# 11_-_CPU_-_POWER.net
KiCad netlist of a schematic drawn in Altium Designer
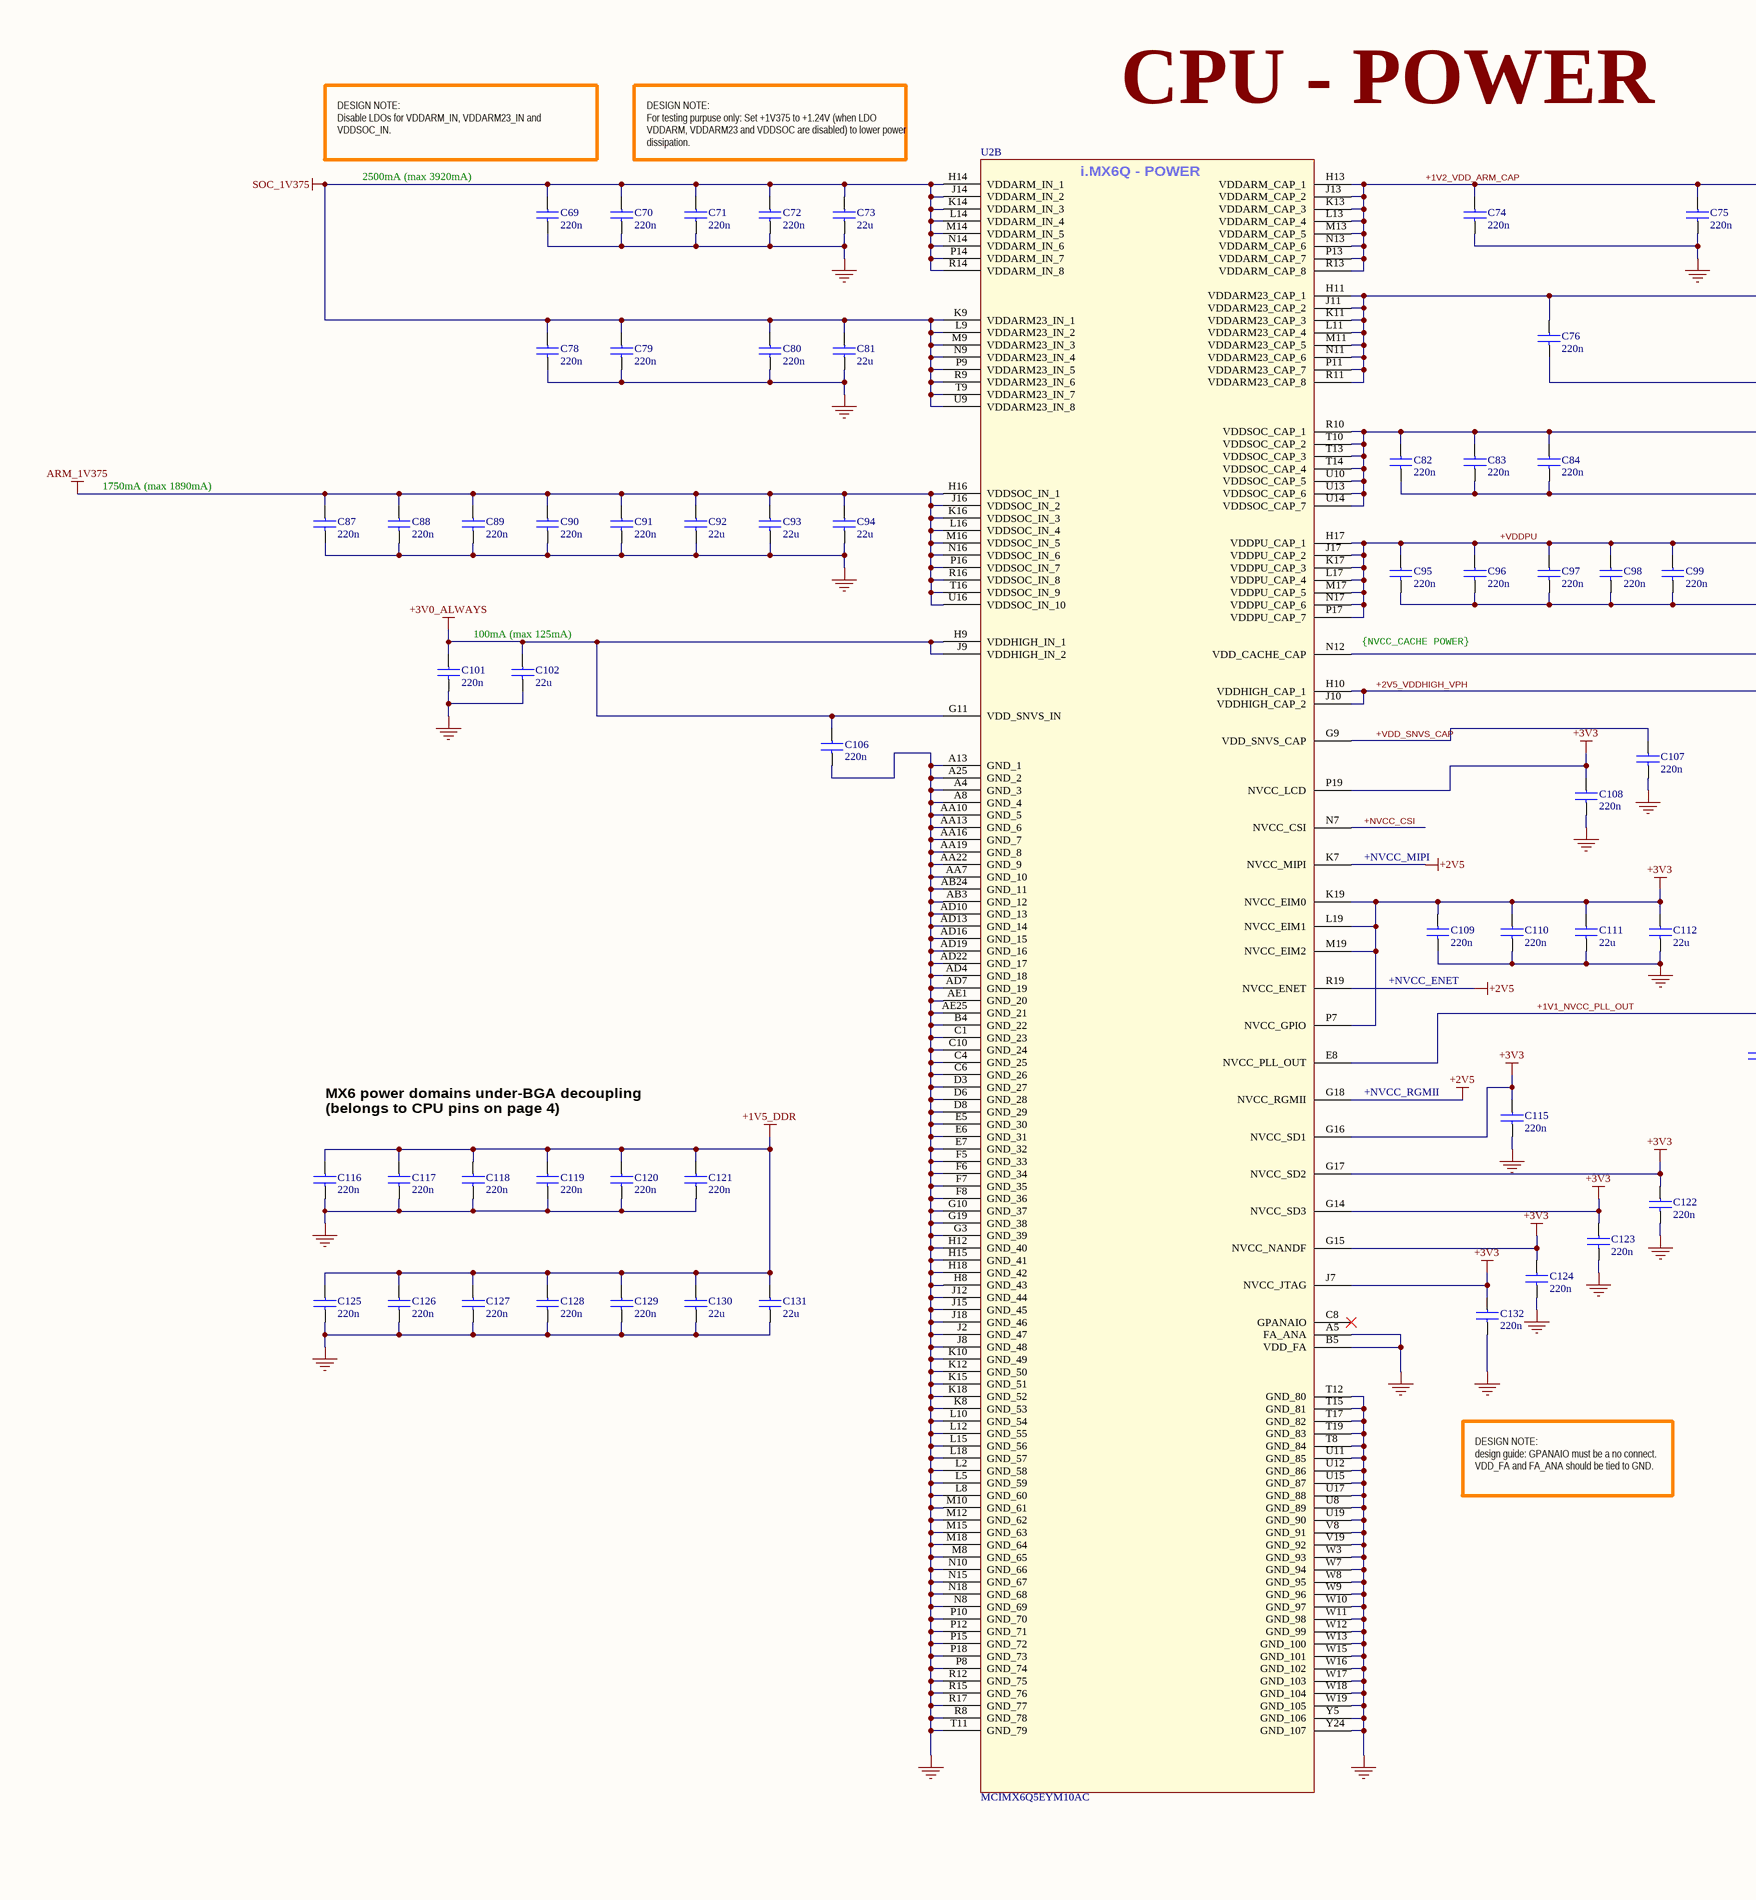
[diagram p0: [11] - CPU - POWER.SchDoc, left]
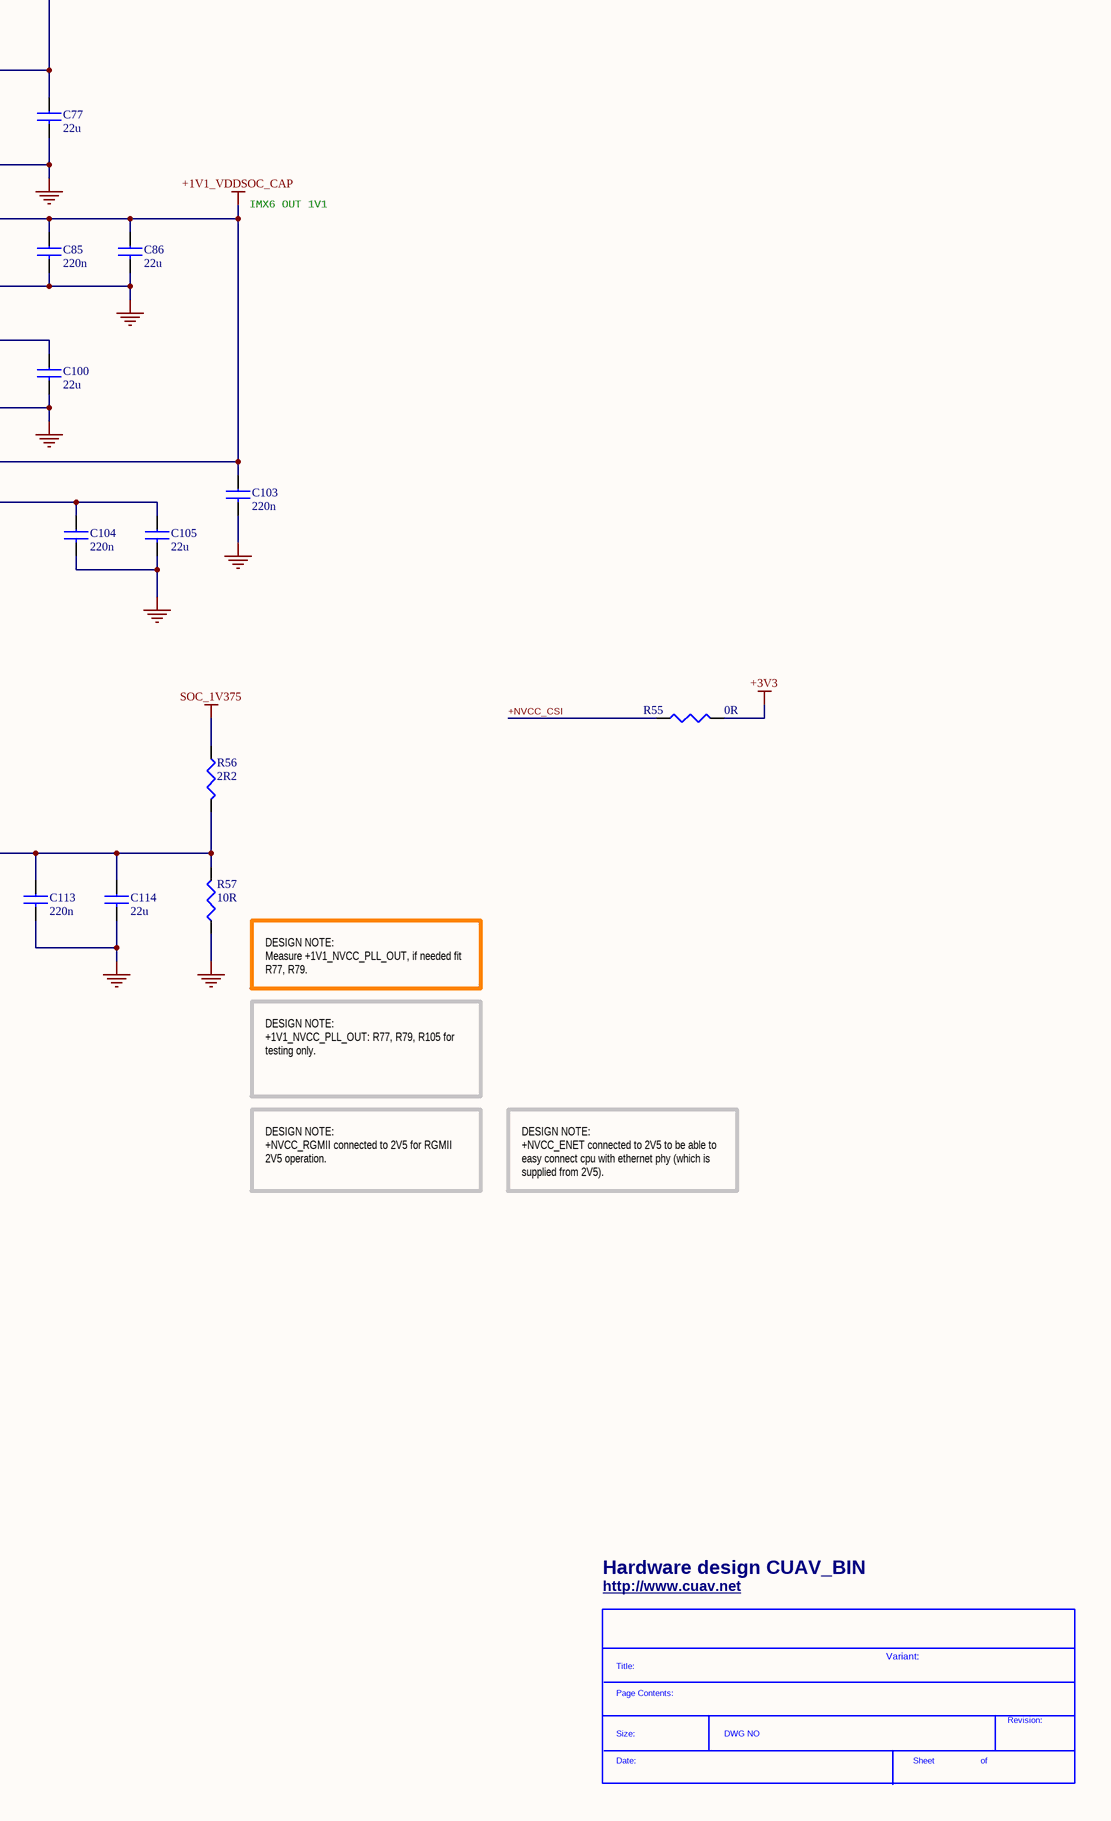
[diagram p1: [11] - CPU - POWER.SchDoc, right]

(export (version "E")
  (design (tool "Eeschema 10.0.6"))
  (components
    (comp (ref "*") (value "SDTitleBlock") (libsource (lib "*") (part "SDTitleBlock")))
    (comp (ref "C69")
      (value "220n")
      (footprint "0402cap")
      (description "CAP CER .22UF 25V X5R 20% 0402")
      (fields
        (field (name "MANUFACTURER") "TDK Corporation")
        (field (name "MANUFACTURER PART NUMBER") "C1005X5R1E224M")
      )
      (libsource (lib "Integrated_Library_RF_FEB_2012") (part "C1005X5R1E224M"))
    )
    (comp (ref "C70")
      (value "220n")
      (footprint "0402cap")
      (description "CAP CER .22UF 25V X5R 20% 0402")
      (fields
        (field (name "MANUFACTURER") "TDK Corporation")
        (field (name "MANUFACTURER PART NUMBER") "C1005X5R1E224M")
      )
      (libsource (lib "Integrated_Library_RF_FEB_2012") (part "C1005X5R1E224M"))
    )
    (comp (ref "C71")
      (value "220n")
      (footprint "0402cap")
      (description "CAP CER .22UF 25V X5R 20% 0402")
      (fields
        (field (name "MANUFACTURER") "TDK Corporation")
        (field (name "MANUFACTURER PART NUMBER") "C1005X5R1E224M")
      )
      (libsource (lib "Integrated_Library_RF_FEB_2012") (part "C1005X5R1E224M"))
    )
    (comp (ref "C72")
      (value "220n")
      (footprint "0402cap")
      (description "CAP CER .22UF 25V X5R 20% 0402")
      (fields
        (field (name "MANUFACTURER") "TDK Corporation")
        (field (name "MANUFACTURER PART NUMBER") "C1005X5R1E224M")
      )
      (libsource (lib "Integrated_Library_RF_FEB_2012") (part "C1005X5R1E224M"))
    )
    (comp (ref "C73")
      (value "22u")
      (footprint "C0603")
      (description "CAP CER 22UF 4V 20% X5R 0603")
      (fields
        (field (name "MANUFACTURER") "Murata Electronics North America")
        (field (name "MANUFACTURER PART NUMBER") "GRM188R60G226MEA0L")
        (field (name ".CHECKED PCB") "RF, used by MM")
        (field (name ".CHECKED SCH") "MM, checked by RF")
        (field (name ".CREATOR") "MM")
      )
      (libsource (lib "Schlib_RF") (part "GRM188R60G226MEA0L"))
    )
    (comp (ref "C74")
      (value "220n")
      (footprint "0402cap")
      (description "CAP CER .22UF 25V X5R 20% 0402")
      (fields
        (field (name "MANUFACTURER") "TDK Corporation")
        (field (name "MANUFACTURER PART NUMBER") "C1005X5R1E224M")
      )
      (libsource (lib "Integrated_Library_RF_FEB_2012") (part "C1005X5R1E224M"))
    )
    (comp (ref "C75")
      (value "220n")
      (footprint "0402cap")
      (description "CAP CER .22UF 25V X5R 20% 0402")
      (fields
        (field (name "MANUFACTURER") "TDK Corporation")
        (field (name "MANUFACTURER PART NUMBER") "C1005X5R1E224M")
      )
      (libsource (lib "Integrated_Library_RF_FEB_2012") (part "C1005X5R1E224M"))
    )
    (comp (ref "C76")
      (value "220n")
      (footprint "0402cap")
      (description "CAP CER .22UF 25V X5R 20% 0402")
      (fields
        (field (name "MANUFACTURER") "TDK Corporation")
        (field (name "MANUFACTURER PART NUMBER") "C1005X5R1E224M")
      )
      (libsource (lib "Integrated_Library_RF_FEB_2012") (part "C1005X5R1E224M"))
    )
    (comp (ref "C77")
      (value "22u")
      (footprint "C0603")
      (description "CAP CER 22UF 4V 20% X5R 0603")
      (fields
        (field (name "MANUFACTURER") "Murata Electronics North America")
        (field (name "MANUFACTURER PART NUMBER") "GRM188R60G226MEA0L")
        (field (name ".CHECKED PCB") "RF, used by MM")
        (field (name ".CHECKED SCH") "MM, checked by RF")
        (field (name ".CREATOR") "MM")
      )
      (libsource (lib "Schlib_RF") (part "GRM188R60G226MEA0L"))
    )
    (comp (ref "C78")
      (value "220n")
      (footprint "0402cap")
      (description "CAP CER .22UF 25V X5R 20% 0402")
      (fields
        (field (name "MANUFACTURER") "TDK Corporation")
        (field (name "MANUFACTURER PART NUMBER") "C1005X5R1E224M")
      )
      (libsource (lib "Integrated_Library_RF_FEB_2012") (part "C1005X5R1E224M"))
    )
    (comp (ref "C79")
      (value "220n")
      (footprint "0402cap")
      (description "CAP CER .22UF 25V X5R 20% 0402")
      (fields
        (field (name "MANUFACTURER") "TDK Corporation")
        (field (name "MANUFACTURER PART NUMBER") "C1005X5R1E224M")
      )
      (libsource (lib "Integrated_Library_RF_FEB_2012") (part "C1005X5R1E224M"))
    )
    (comp (ref "C80")
      (value "220n")
      (footprint "0402cap")
      (description "CAP CER .22UF 25V X5R 20% 0402")
      (fields
        (field (name "MANUFACTURER") "TDK Corporation")
        (field (name "MANUFACTURER PART NUMBER") "C1005X5R1E224M")
      )
      (libsource (lib "Integrated_Library_RF_FEB_2012") (part "C1005X5R1E224M"))
    )
    (comp (ref "C81")
      (value "22u")
      (footprint "C0603")
      (description "CAP CER 22UF 4V 20% X5R 0603")
      (fields
        (field (name "MANUFACTURER") "Murata Electronics North America")
        (field (name "MANUFACTURER PART NUMBER") "GRM188R60G226MEA0L")
        (field (name ".CHECKED PCB") "RF, used by MM")
        (field (name ".CHECKED SCH") "MM, checked by RF")
        (field (name ".CREATOR") "MM")
      )
      (libsource (lib "Schlib_RF") (part "GRM188R60G226MEA0L"))
    )
    (comp (ref "C82")
      (value "220n")
      (footprint "0402cap")
      (description "CAP CER .22UF 25V X5R 20% 0402")
      (fields
        (field (name "MANUFACTURER") "TDK Corporation")
        (field (name "MANUFACTURER PART NUMBER") "C1005X5R1E224M")
      )
      (libsource (lib "Integrated_Library_RF_FEB_2012") (part "C1005X5R1E224M"))
    )
    (comp (ref "C83")
      (value "220n")
      (footprint "0402cap")
      (description "CAP CER .22UF 25V X5R 20% 0402")
      (fields
        (field (name "MANUFACTURER") "TDK Corporation")
        (field (name "MANUFACTURER PART NUMBER") "C1005X5R1E224M")
      )
      (libsource (lib "Integrated_Library_RF_FEB_2012") (part "C1005X5R1E224M"))
    )
    (comp (ref "C84")
      (value "220n")
      (footprint "0402cap")
      (description "CAP CER .22UF 25V X5R 20% 0402")
      (fields
        (field (name "MANUFACTURER") "TDK Corporation")
        (field (name "MANUFACTURER PART NUMBER") "C1005X5R1E224M")
      )
      (libsource (lib "Integrated_Library_RF_FEB_2012") (part "C1005X5R1E224M"))
    )
    (comp (ref "C85")
      (value "220n")
      (footprint "0402cap")
      (description "CAP CER .22UF 25V X5R 20% 0402")
      (fields
        (field (name "MANUFACTURER") "TDK Corporation")
        (field (name "MANUFACTURER PART NUMBER") "C1005X5R1E224M")
      )
      (libsource (lib "Integrated_Library_RF_FEB_2012") (part "C1005X5R1E224M"))
    )
    (comp (ref "C86")
      (value "22u")
      (footprint "C0603")
      (description "CAP CER 22UF 4V 20% X5R 0603")
      (fields
        (field (name "MANUFACTURER") "Murata Electronics North America")
        (field (name "MANUFACTURER PART NUMBER") "GRM188R60G226MEA0L")
        (field (name ".CHECKED PCB") "RF, used by MM")
        (field (name ".CHECKED SCH") "MM, checked by RF")
        (field (name ".CREATOR") "MM")
      )
      (libsource (lib "Schlib_RF") (part "GRM188R60G226MEA0L"))
    )
    (comp (ref "C87")
      (value "220n")
      (footprint "0402cap")
      (description "CAP CER .22UF 25V X5R 20% 0402")
      (fields
        (field (name "MANUFACTURER") "TDK Corporation")
        (field (name "MANUFACTURER PART NUMBER") "C1005X5R1E224M")
      )
      (libsource (lib "Integrated_Library_RF_FEB_2012") (part "C1005X5R1E224M"))
    )
    (comp (ref "C88")
      (value "220n")
      (footprint "0402cap")
      (description "CAP CER .22UF 25V X5R 20% 0402")
      (fields
        (field (name "MANUFACTURER") "TDK Corporation")
        (field (name "MANUFACTURER PART NUMBER") "C1005X5R1E224M")
      )
      (libsource (lib "Integrated_Library_RF_FEB_2012") (part "C1005X5R1E224M"))
    )
    (comp (ref "C89")
      (value "220n")
      (footprint "0402cap")
      (description "CAP CER .22UF 25V X5R 20% 0402")
      (fields
        (field (name "MANUFACTURER") "TDK Corporation")
        (field (name "MANUFACTURER PART NUMBER") "C1005X5R1E224M")
      )
      (libsource (lib "Integrated_Library_RF_FEB_2012") (part "C1005X5R1E224M"))
    )
    (comp (ref "C90")
      (value "220n")
      (footprint "0402cap")
      (description "CAP CER .22UF 25V X5R 20% 0402")
      (fields
        (field (name "MANUFACTURER") "TDK Corporation")
        (field (name "MANUFACTURER PART NUMBER") "C1005X5R1E224M")
      )
      (libsource (lib "Integrated_Library_RF_FEB_2012") (part "C1005X5R1E224M"))
    )
    (comp (ref "C91")
      (value "220n")
      (footprint "0402cap")
      (description "CAP CER .22UF 25V X5R 20% 0402")
      (fields
        (field (name "MANUFACTURER") "TDK Corporation")
        (field (name "MANUFACTURER PART NUMBER") "C1005X5R1E224M")
      )
      (libsource (lib "Integrated_Library_RF_FEB_2012") (part "C1005X5R1E224M"))
    )
    (comp (ref "C92")
      (value "22u")
      (footprint "C0603")
      (description "CAP CER 22UF 4V 20% X5R 0603")
      (fields
        (field (name "MANUFACTURER") "Murata Electronics North America")
        (field (name "MANUFACTURER PART NUMBER") "GRM188R60G226MEA0L")
        (field (name ".CHECKED PCB") "RF, used by MM")
        (field (name ".CHECKED SCH") "MM, checked by RF")
        (field (name ".CREATOR") "MM")
      )
      (libsource (lib "Schlib_RF") (part "GRM188R60G226MEA0L"))
    )
    (comp (ref "C93")
      (value "22u")
      (footprint "C0603")
      (description "CAP CER 22UF 4V 20% X5R 0603")
      (fields
        (field (name "MANUFACTURER") "Murata Electronics North America")
        (field (name "MANUFACTURER PART NUMBER") "GRM188R60G226MEA0L")
        (field (name ".CHECKED PCB") "RF, used by MM")
        (field (name ".CHECKED SCH") "MM, checked by RF")
        (field (name ".CREATOR") "MM")
      )
      (libsource (lib "Schlib_RF") (part "GRM188R60G226MEA0L"))
    )
    (comp (ref "C94")
      (value "22u")
      (footprint "C0603")
      (description "CAP CER 22UF 4V 20% X5R 0603")
      (fields
        (field (name "MANUFACTURER") "Murata Electronics North America")
        (field (name "MANUFACTURER PART NUMBER") "GRM188R60G226MEA0L")
        (field (name ".CHECKED PCB") "RF, used by MM")
        (field (name ".CHECKED SCH") "MM, checked by RF")
        (field (name ".CREATOR") "MM")
      )
      (libsource (lib "Schlib_RF") (part "GRM188R60G226MEA0L"))
    )
    (comp (ref "C95")
      (value "220n")
      (footprint "0402cap")
      (description "CAP CER .22UF 25V X5R 20% 0402")
      (fields
        (field (name "MANUFACTURER") "TDK Corporation")
        (field (name "MANUFACTURER PART NUMBER") "C1005X5R1E224M")
      )
      (libsource (lib "Integrated_Library_RF_FEB_2012") (part "C1005X5R1E224M"))
    )
    (comp (ref "C96")
      (value "220n")
      (footprint "0402cap")
      (description "CAP CER .22UF 25V X5R 20% 0402")
      (fields
        (field (name "MANUFACTURER") "TDK Corporation")
        (field (name "MANUFACTURER PART NUMBER") "C1005X5R1E224M")
      )
      (libsource (lib "Integrated_Library_RF_FEB_2012") (part "C1005X5R1E224M"))
    )
    (comp (ref "C97")
      (value "220n")
      (footprint "0402cap")
      (description "CAP CER .22UF 25V X5R 20% 0402")
      (fields
        (field (name "MANUFACTURER") "TDK Corporation")
        (field (name "MANUFACTURER PART NUMBER") "C1005X5R1E224M")
      )
      (libsource (lib "Integrated_Library_RF_FEB_2012") (part "C1005X5R1E224M"))
    )
    (comp (ref "C98")
      (value "220n")
      (footprint "0402cap")
      (description "CAP CER .22UF 25V X5R 20% 0402")
      (fields
        (field (name "MANUFACTURER") "TDK Corporation")
        (field (name "MANUFACTURER PART NUMBER") "C1005X5R1E224M")
      )
      (libsource (lib "Integrated_Library_RF_FEB_2012") (part "C1005X5R1E224M"))
    )
    (comp (ref "C99")
      (value "220n")
      (footprint "0402cap")
      (description "CAP CER .22UF 25V X5R 20% 0402")
      (fields
        (field (name "MANUFACTURER") "TDK Corporation")
        (field (name "MANUFACTURER PART NUMBER") "C1005X5R1E224M")
      )
      (libsource (lib "Integrated_Library_RF_FEB_2012") (part "C1005X5R1E224M"))
    )
    (comp (ref "C100")
      (value "22u")
      (footprint "C0603")
      (description "CAP CER 22UF 4V 20% X5R 0603")
      (fields
        (field (name "MANUFACTURER") "Murata Electronics North America")
        (field (name "MANUFACTURER PART NUMBER") "GRM188R60G226MEA0L")
        (field (name ".CHECKED PCB") "RF, used by MM")
        (field (name ".CHECKED SCH") "MM, checked by RF")
        (field (name ".CREATOR") "MM")
      )
      (libsource (lib "Schlib_RF") (part "GRM188R60G226MEA0L"))
    )
    (comp (ref "C101")
      (value "220n")
      (footprint "0402cap")
      (description "CAP CER .22UF 25V X5R 20% 0402")
      (fields
        (field (name "MANUFACTURER") "TDK Corporation")
        (field (name "MANUFACTURER PART NUMBER") "C1005X5R1E224M")
      )
      (libsource (lib "Integrated_Library_RF_FEB_2012") (part "C1005X5R1E224M"))
    )
    (comp (ref "C102")
      (value "22u")
      (footprint "C0805")
      (description "CAP CER 22UF 16V 10% X5R 0805")
      (fields
        (field (name "MANUFACTURER") "TDK Corporation")
        (field (name "MANUFACTURER PART NUMBER") "C2012X5R1C226K")
        (field (name ".CHECKED PCB") "RF")
        (field (name ".CHECKED SCH") "RF")
      )
      (libsource (lib "Integrated_Library_RF_FEB_2012") (part "C2012X5R1C226K"))
    )
    (comp (ref "C103")
      (value "220n")
      (footprint "0402cap")
      (description "CAP CER .22UF 25V X5R 20% 0402")
      (fields
        (field (name "MANUFACTURER") "TDK Corporation")
        (field (name "MANUFACTURER PART NUMBER") "C1005X5R1E224M")
      )
      (libsource (lib "Integrated_Library_RF_FEB_2012") (part "C1005X5R1E224M"))
    )
    (comp (ref "C104")
      (value "220n")
      (footprint "0402cap")
      (description "CAP CER .22UF 25V X5R 20% 0402")
      (fields
        (field (name "MANUFACTURER") "TDK Corporation")
        (field (name "MANUFACTURER PART NUMBER") "C1005X5R1E224M")
      )
      (libsource (lib "Integrated_Library_RF_FEB_2012") (part "C1005X5R1E224M"))
    )
    (comp (ref "C105")
      (value "22u")
      (footprint "0805cap")
      (description "CAP CER 22UF 16V 10% X5R 0805")
      (fields
        (field (name "MANUFACTURER") "TDK Corporation")
        (field (name "MANUFACTURER PART NUMBER") "C2012X5R1C226K")
        (field (name ".CHECKED PCB") "RF")
        (field (name ".CHECKED SCH") "RF")
      )
      (libsource (lib "Integrated_Library_RF_FEB_2012") (part "C2012X5R1C226K"))
    )
    (comp (ref "C106")
      (value "220n")
      (footprint "0402cap")
      (description "CAP CER .22UF 25V X5R 20% 0402")
      (fields
        (field (name "MANUFACTURER") "TDK Corporation")
        (field (name "MANUFACTURER PART NUMBER") "C1005X5R1E224M")
      )
      (libsource (lib "Integrated_Library_RF_FEB_2012") (part "C1005X5R1E224M"))
    )
    (comp (ref "C107")
      (value "220n")
      (footprint "0402cap")
      (description "CAP CER .22UF 25V X5R 20% 0402")
      (fields
        (field (name "MANUFACTURER") "TDK Corporation")
        (field (name "MANUFACTURER PART NUMBER") "C1005X5R1E224M")
      )
      (libsource (lib "Integrated_Library_RF_FEB_2012") (part "C1005X5R1E224M"))
    )
    (comp (ref "C108")
      (value "220n")
      (footprint "0402cap")
      (description "CAP CER .22UF 25V X5R 20% 0402")
      (fields
        (field (name "MANUFACTURER") "TDK Corporation")
        (field (name "MANUFACTURER PART NUMBER") "C1005X5R1E224M")
      )
      (libsource (lib "Integrated_Library_RF_FEB_2012") (part "C1005X5R1E224M"))
    )
    (comp (ref "C109")
      (value "220n")
      (footprint "0402cap")
      (description "CAP CER .22UF 25V X5R 20% 0402")
      (fields
        (field (name "MANUFACTURER") "TDK Corporation")
        (field (name "MANUFACTURER PART NUMBER") "C1005X5R1E224M")
      )
      (libsource (lib "Integrated_Library_RF_FEB_2012") (part "C1005X5R1E224M"))
    )
    (comp (ref "C110")
      (value "220n")
      (footprint "0402cap")
      (description "CAP CER .22UF 25V X5R 20% 0402")
      (fields
        (field (name "MANUFACTURER") "TDK Corporation")
        (field (name "MANUFACTURER PART NUMBER") "C1005X5R1E224M")
      )
      (libsource (lib "Integrated_Library_RF_FEB_2012") (part "C1005X5R1E224M"))
    )
    (comp (ref "C111")
      (value "22u")
      (footprint "0805cap")
      (description "CAP CER 22UF 16V 10% X5R 0805")
      (fields
        (field (name "MANUFACTURER") "TDK Corporation")
        (field (name "MANUFACTURER PART NUMBER") "C2012X5R1C226K")
        (field (name ".CHECKED PCB") "RF")
        (field (name ".CHECKED SCH") "RF")
      )
      (libsource (lib "Integrated_Library_RF_FEB_2012") (part "C2012X5R1C226K"))
    )
    (comp (ref "C112")
      (value "22u")
      (footprint "0805cap")
      (description "CAP CER 22UF 16V 10% X5R 0805")
      (fields
        (field (name "MANUFACTURER") "TDK Corporation")
        (field (name "MANUFACTURER PART NUMBER") "C2012X5R1C226K")
        (field (name ".CHECKED PCB") "RF")
        (field (name ".CHECKED SCH") "RF")
      )
      (libsource (lib "Integrated_Library_RF_FEB_2012") (part "C2012X5R1C226K"))
    )
    (comp (ref "C113")
      (value "220n")
      (footprint "C0402")
      (description "CAP CER .22UF 25V X5R 20% 0402")
      (fields
        (field (name "MANUFACTURER") "TDK Corporation")
        (field (name "MANUFACTURER PART NUMBER") "C1005X5R1E224M")
      )
      (libsource (lib "Integrated_Library_RF_FEB_2012") (part "C1005X5R1E224M"))
    )
    (comp (ref "C114")
      (value "22u")
      (footprint "C0603")
      (description "CAP CER 22UF 4V 20% X5R 0603")
      (fields
        (field (name "MANUFACTURER") "Murata Electronics North America")
        (field (name "MANUFACTURER PART NUMBER") "GRM188R60G226MEA0L")
        (field (name ".CHECKED PCB") "RF, used by MM")
        (field (name ".CHECKED SCH") "MM, checked by RF")
        (field (name ".CREATOR") "MM")
      )
      (libsource (lib "Schlib_RF") (part "GRM188R60G226MEA0L"))
    )
    (comp (ref "C115")
      (value "220n")
      (footprint "0402cap")
      (description "CAP CER .22UF 25V X5R 20% 0402")
      (fields
        (field (name "MANUFACTURER") "TDK Corporation")
        (field (name "MANUFACTURER PART NUMBER") "C1005X5R1E224M")
      )
      (libsource (lib "Integrated_Library_RF_FEB_2012") (part "C1005X5R1E224M"))
    )
    (comp (ref "C116")
      (value "220n")
      (footprint "0402cap")
      (description "CAP CER .22UF 25V X5R 20% 0402")
      (fields
        (field (name "MANUFACTURER") "TDK Corporation")
        (field (name "MANUFACTURER PART NUMBER") "C1005X5R1E224M")
      )
      (libsource (lib "Integrated_Library_RF_FEB_2012") (part "C1005X5R1E224M"))
    )
    (comp (ref "C117")
      (value "220n")
      (footprint "0402cap")
      (description "CAP CER .22UF 25V X5R 20% 0402")
      (fields
        (field (name "MANUFACTURER") "TDK Corporation")
        (field (name "MANUFACTURER PART NUMBER") "C1005X5R1E224M")
      )
      (libsource (lib "Integrated_Library_RF_FEB_2012") (part "C1005X5R1E224M"))
    )
    (comp (ref "C118")
      (value "220n")
      (footprint "0402cap")
      (description "CAP CER .22UF 25V X5R 20% 0402")
      (fields
        (field (name "MANUFACTURER") "TDK Corporation")
        (field (name "MANUFACTURER PART NUMBER") "C1005X5R1E224M")
      )
      (libsource (lib "Integrated_Library_RF_FEB_2012") (part "C1005X5R1E224M"))
    )
    (comp (ref "C119")
      (value "220n")
      (footprint "0402cap")
      (description "CAP CER .22UF 25V X5R 20% 0402")
      (fields
        (field (name "MANUFACTURER") "TDK Corporation")
        (field (name "MANUFACTURER PART NUMBER") "C1005X5R1E224M")
      )
      (libsource (lib "Integrated_Library_RF_FEB_2012") (part "C1005X5R1E224M"))
    )
    (comp (ref "C120")
      (value "220n")
      (footprint "0402cap")
      (description "CAP CER .22UF 25V X5R 20% 0402")
      (fields
        (field (name "MANUFACTURER") "TDK Corporation")
        (field (name "MANUFACTURER PART NUMBER") "C1005X5R1E224M")
      )
      (libsource (lib "Integrated_Library_RF_FEB_2012") (part "C1005X5R1E224M"))
    )
    (comp (ref "C121")
      (value "220n")
      (footprint "0402cap")
      (description "CAP CER .22UF 25V X5R 20% 0402")
      (fields
        (field (name "MANUFACTURER") "TDK Corporation")
        (field (name "MANUFACTURER PART NUMBER") "C1005X5R1E224M")
      )
      (libsource (lib "Integrated_Library_RF_FEB_2012") (part "C1005X5R1E224M"))
    )
    (comp (ref "C122")
      (value "220n")
      (footprint "0402cap")
      (description "CAP CER .22UF 25V X5R 20% 0402")
      (fields
        (field (name "MANUFACTURER") "TDK Corporation")
        (field (name "MANUFACTURER PART NUMBER") "C1005X5R1E224M")
      )
      (libsource (lib "Integrated_Library_RF_FEB_2012") (part "C1005X5R1E224M"))
    )
    (comp (ref "C123")
      (value "220n")
      (footprint "0402cap")
      (description "CAP CER .22UF 25V X5R 20% 0402")
      (fields
        (field (name "MANUFACTURER") "TDK Corporation")
        (field (name "MANUFACTURER PART NUMBER") "C1005X5R1E224M")
      )
      (libsource (lib "Integrated_Library_RF_FEB_2012") (part "C1005X5R1E224M"))
    )
    (comp (ref "C124")
      (value "220n")
      (footprint "0402cap")
      (description "CAP CER .22UF 25V X5R 20% 0402")
      (fields
        (field (name "MANUFACTURER") "TDK Corporation")
        (field (name "MANUFACTURER PART NUMBER") "C1005X5R1E224M")
      )
      (libsource (lib "Integrated_Library_RF_FEB_2012") (part "C1005X5R1E224M"))
    )
    (comp (ref "C125")
      (value "220n")
      (footprint "0402cap")
      (description "CAP CER .22UF 25V X5R 20% 0402")
      (fields
        (field (name "MANUFACTURER") "TDK Corporation")
        (field (name "MANUFACTURER PART NUMBER") "C1005X5R1E224M")
      )
      (libsource (lib "Integrated_Library_RF_FEB_2012") (part "C1005X5R1E224M"))
    )
    (comp (ref "C126")
      (value "220n")
      (footprint "0402cap")
      (description "CAP CER .22UF 25V X5R 20% 0402")
      (fields
        (field (name "MANUFACTURER") "TDK Corporation")
        (field (name "MANUFACTURER PART NUMBER") "C1005X5R1E224M")
      )
      (libsource (lib "Integrated_Library_RF_FEB_2012") (part "C1005X5R1E224M"))
    )
    (comp (ref "C127")
      (value "220n")
      (footprint "0402cap")
      (description "CAP CER .22UF 25V X5R 20% 0402")
      (fields
        (field (name "MANUFACTURER") "TDK Corporation")
        (field (name "MANUFACTURER PART NUMBER") "C1005X5R1E224M")
      )
      (libsource (lib "Integrated_Library_RF_FEB_2012") (part "C1005X5R1E224M"))
    )
    (comp (ref "C128")
      (value "220n")
      (footprint "0402cap")
      (description "CAP CER .22UF 25V X5R 20% 0402")
      (fields
        (field (name "MANUFACTURER") "TDK Corporation")
        (field (name "MANUFACTURER PART NUMBER") "C1005X5R1E224M")
      )
      (libsource (lib "Integrated_Library_RF_FEB_2012") (part "C1005X5R1E224M"))
    )
    (comp (ref "C129")
      (value "220n")
      (footprint "0402cap")
      (description "CAP CER .22UF 25V X5R 20% 0402")
      (fields
        (field (name "MANUFACTURER") "TDK Corporation")
        (field (name "MANUFACTURER PART NUMBER") "C1005X5R1E224M")
      )
      (libsource (lib "Integrated_Library_RF_FEB_2012") (part "C1005X5R1E224M"))
    )
    (comp (ref "C130")
      (value "22u")
      (footprint "C0603")
      (description "CAP CER 22UF 4V 20% X5R 0603")
      (fields
        (field (name "MANUFACTURER") "Murata Electronics North America")
        (field (name "MANUFACTURER PART NUMBER") "GRM188R60G226MEA0L")
        (field (name ".CHECKED PCB") "RF, used by MM")
        (field (name ".CHECKED SCH") "MM, checked by RF")
        (field (name ".CREATOR") "MM")
      )
      (libsource (lib "Schlib_RF") (part "GRM188R60G226MEA0L"))
    )
    (comp (ref "C131")
      (value "22u")
      (footprint "C0603")
      (description "CAP CER 22UF 4V 20% X5R 0603")
      (fields
        (field (name "MANUFACTURER") "Murata Electronics North America")
        (field (name "MANUFACTURER PART NUMBER") "GRM188R60G226MEA0L")
        (field (name ".CHECKED PCB") "RF, used by MM")
        (field (name ".CHECKED SCH") "MM, checked by RF")
        (field (name ".CREATOR") "MM")
      )
      (libsource (lib "Schlib_RF") (part "GRM188R60G226MEA0L"))
    )
    (comp (ref "C132")
      (value "220n")
      (footprint "0402cap")
      (description "CAP CER .22UF 25V X5R 20% 0402")
      (fields
        (field (name "MANUFACTURER") "TDK Corporation")
        (field (name "MANUFACTURER PART NUMBER") "C1005X5R1E224M")
      )
      (libsource (lib "Integrated_Library_RF_FEB_2012") (part "C1005X5R1E224M"))
    )
    (comp (ref "R55")
      (value "0R")
      (footprint "R0402")
      (description "RES 0.0 OHM 1/16W 0402 SMD")
      (fields
        (field (name "MANUFACTURER") "Yageo")
        (field (name "MANUFACTURER PART NUMBER") "RC0402JR-070RL")
      )
      (libsource (lib "Integrated_Library_RF_FEB_2012") (part "RC0402JR-070RL"))
    )
    (comp (ref "R56")
      (value "2R2")
      (footprint "R0402")
      (description "RES 2.20 OHM 1/16W 1% 0402 SMD")
      (fields
        (field (name "MANUFACTURER") "Vishay Dale")
        (field (name "MANUFACTURER PART NUMBER") "CRCW04022R20FKED")
        (field (name ".CHECKED PCB") "RF")
        (field (name ".CHECKED SCH") "RF")
      )
      (libsource (lib "Integrated_Library_RF_FEB_2012") (part "CRCW04022R20FKED"))
    )
    (comp (ref "R57")
      (value "10R")
      (footprint "R0402")
      (description "RES 10.0 OHM 1/16W 1% 0402 SMD")
      (fields
        (field (name "MANUFACTURER") "Yageo")
        (field (name "MANUFACTURER PART NUMBER") "RC0402FR-0710RL")
      )
      (libsource (lib "Integrated_Library_RF_FEB_2012") (part "RC0402FR-0710RL"))
    )
    (comp (ref "U2")
      (value "MCIMX6Q5EYM10AC")
      (footprint "PBGA624")
      (description "IC MCU 32BIT ARM QUAD 624FCBGA")
      (fields
        (field (name "MANUFACTURER") "Freescale Semiconductor")
        (field (name ".CREATOR") "MM")
        (field (name ".CHECKED PCB") "MM, checked by RF")
        (field (name ".CHECKED SCH") "MM")
      )
      (libsource (lib "Schlib_RF") (part "MCIMX6Q5EYM10AC"))
    )
  )
  (nets
    (net (code "1") (name "+1V1_VDDSOC_CAP") (class "Default")
      (node (ref "C103") (pin "1") (pinfunction "1_1") (pintype "passive"))
      (node (ref "C82") (pin "1") (pinfunction "1_1") (pintype "passive"))
      (node (ref "C83") (pin "1") (pinfunction "1_1") (pintype "passive"))
      (node (ref "C84") (pin "1") (pinfunction "1_1") (pintype "passive"))
      (node (ref "C85") (pin "1") (pinfunction "1_1") (pintype "passive"))
      (node (ref "C86") (pin "1") (pinfunction "1_1") (pintype "passive"))
      (node (ref "U2") (pin "N12") (pinfunction "VDD_CACHE_CAP_N12") (pintype "power_in"))
      (node (ref "U2") (pin "R10") (pinfunction "VDDSOC_CAP_1_R10") (pintype "power_in"))
      (node (ref "U2") (pin "T10") (pinfunction "VDDSOC_CAP_2_T10") (pintype "power_in"))
      (node (ref "U2") (pin "T13") (pinfunction "VDDSOC_CAP_3_T13") (pintype "power_in"))
      (node (ref "U2") (pin "T14") (pinfunction "VDDSOC_CAP_4_T14") (pintype "power_in"))
      (node (ref "U2") (pin "U10") (pinfunction "VDDSOC_CAP_5_U10") (pintype "power_in"))
      (node (ref "U2") (pin "U13") (pinfunction "VDDSOC_CAP_6_U13") (pintype "power_in"))
      (node (ref "U2") (pin "U14") (pinfunction "VDDSOC_CAP_7_U14") (pintype "power_in"))
    )
    (net (code "2") (name "+1V5_DDR") (class "Default")
      (node (ref "C116") (pin "1") (pinfunction "1_1") (pintype "passive"))
      (node (ref "C117") (pin "1") (pinfunction "1_1") (pintype "passive"))
      (node (ref "C118") (pin "1") (pinfunction "1_1") (pintype "passive"))
      (node (ref "C119") (pin "1") (pinfunction "1_1") (pintype "passive"))
      (node (ref "C120") (pin "1") (pinfunction "1_1") (pintype "passive"))
      (node (ref "C121") (pin "1") (pinfunction "1_1") (pintype "passive"))
      (node (ref "C125") (pin "1") (pinfunction "1_1") (pintype "passive"))
      (node (ref "C126") (pin "1") (pinfunction "1_1") (pintype "passive"))
      (node (ref "C127") (pin "1") (pinfunction "1_1") (pintype "passive"))
      (node (ref "C128") (pin "1") (pinfunction "1_1") (pintype "passive"))
      (node (ref "C129") (pin "1") (pinfunction "1_1") (pintype "passive"))
      (node (ref "C130") (pin "1") (pinfunction "1_1") (pintype "passive"))
      (node (ref "C131") (pin "1") (pinfunction "1_1") (pintype "passive"))
    )
    (net (code "3") (name "+2V5") (class "Default")
      (node (ref "U2") (pin "G18") (pinfunction "NVCC_RGMII_G18") (pintype "power_in"))
      (node (ref "U2") (pin "K7") (pinfunction "NVCC_MIPI_K7") (pintype "power_in"))
      (node (ref "U2") (pin "R19") (pinfunction "NVCC_ENET_R19") (pintype "power_in"))
    )
    (net (code "4") (name "+3V0_ALWAYS") (class "Default")
      (node (ref "C101") (pin "1") (pinfunction "1_1") (pintype "passive"))
      (node (ref "C102") (pin "1") (pinfunction "1_1") (pintype "passive"))
      (node (ref "C106") (pin "1") (pinfunction "1_1") (pintype "passive"))
      (node (ref "U2") (pin "G11") (pinfunction "VDD_SNVS_IN_G11") (pintype "power_in"))
      (node (ref "U2") (pin "H9") (pinfunction "VDDHIGH_IN_1_H9") (pintype "power_in"))
      (node (ref "U2") (pin "J9") (pinfunction "VDDHIGH_IN_2_J9") (pintype "power_in"))
    )
    (net (code "5") (name "+3V3") (class "Default")
      (node (ref "C108") (pin "1") (pinfunction "1_1") (pintype "passive"))
      (node (ref "C109") (pin "1") (pinfunction "1_1") (pintype "passive"))
      (node (ref "C110") (pin "1") (pinfunction "1_1") (pintype "passive"))
      (node (ref "C111") (pin "1") (pinfunction "1_1") (pintype "passive"))
      (node (ref "C112") (pin "1") (pinfunction "1_1") (pintype "passive"))
      (node (ref "C115") (pin "1") (pinfunction "1_1") (pintype "passive"))
      (node (ref "C122") (pin "1") (pinfunction "1_1") (pintype "passive"))
      (node (ref "C123") (pin "1") (pinfunction "1_1") (pintype "passive"))
      (node (ref "C124") (pin "1") (pinfunction "1_1") (pintype "passive"))
      (node (ref "C132") (pin "1") (pinfunction "1_1") (pintype "passive"))
      (node (ref "R55") (pin "2") (pinfunction "2_2") (pintype "passive"))
      (node (ref "U2") (pin "G14") (pinfunction "NVCC_SD3_G14") (pintype "power_in"))
      (node (ref "U2") (pin "G15") (pinfunction "NVCC_NANDF_G15") (pintype "power_in"))
      (node (ref "U2") (pin "G16") (pinfunction "NVCC_SD1_G16") (pintype "power_in"))
      (node (ref "U2") (pin "G17") (pinfunction "NVCC_SD2_G17") (pintype "power_in"))
      (node (ref "U2") (pin "J7") (pinfunction "NVCC_JTAG_J7") (pintype "power_in"))
      (node (ref "U2") (pin "K19") (pinfunction "NVCC_EIM0_K19") (pintype "power_in"))
      (node (ref "U2") (pin "L19") (pinfunction "NVCC_EIM1_L19") (pintype "power_in"))
      (node (ref "U2") (pin "M19") (pinfunction "NVCC_EIM2_M19") (pintype "power_in"))
      (node (ref "U2") (pin "P19") (pinfunction "NVCC_LCD_P19") (pintype "power_in"))
      (node (ref "U2") (pin "P7") (pinfunction "NVCC_GPIO_P7") (pintype "power_in"))
    )
    (net (code "6") (name "/+1V1_NVCC_PLL_OUT") (class "Default")
      (node (ref "C113") (pin "1") (pinfunction "1_1") (pintype "passive"))
      (node (ref "C114") (pin "1") (pinfunction "1_1") (pintype "passive"))
      (node (ref "R56") (pin "2") (pinfunction "2_2") (pintype "passive"))
      (node (ref "R57") (pin "2") (pinfunction "2_2") (pintype "passive"))
      (node (ref "U2") (pin "E8") (pinfunction "NVCC_PLL_OUT_E8") (pintype "power_in"))
    )
    (net (code "7") (name "/+1V2_VDD_ARM_CAP") (class "Default")
      (node (ref "C74") (pin "1") (pinfunction "1_1") (pintype "passive"))
      (node (ref "C75") (pin "1") (pinfunction "1_1") (pintype "passive"))
      (node (ref "C76") (pin "1") (pinfunction "1_1") (pintype "passive"))
      (node (ref "C77") (pin "1") (pinfunction "1_1") (pintype "passive"))
      (node (ref "U2") (pin "H11") (pinfunction "VDDARM23_CAP_1_H11") (pintype "power_in"))
      (node (ref "U2") (pin "H13") (pinfunction "VDDARM_CAP_1_H13") (pintype "power_in"))
      (node (ref "U2") (pin "J11") (pinfunction "VDDARM23_CAP_2_J11") (pintype "power_in"))
      (node (ref "U2") (pin "J13") (pinfunction "VDDARM_CAP_2_J13") (pintype "power_in"))
      (node (ref "U2") (pin "K11") (pinfunction "VDDARM23_CAP_3_K11") (pintype "power_in"))
      (node (ref "U2") (pin "K13") (pinfunction "VDDARM_CAP_3_K13") (pintype "power_in"))
      (node (ref "U2") (pin "L11") (pinfunction "VDDARM23_CAP_4_L11") (pintype "power_in"))
      (node (ref "U2") (pin "L13") (pinfunction "VDDARM_CAP_4_L13") (pintype "power_in"))
      (node (ref "U2") (pin "M11") (pinfunction "VDDARM23_CAP_5_M11") (pintype "power_in"))
      (node (ref "U2") (pin "M13") (pinfunction "VDDARM_CAP_5_M13") (pintype "power_in"))
      (node (ref "U2") (pin "N11") (pinfunction "VDDARM23_CAP_6_N11") (pintype "power_in"))
      (node (ref "U2") (pin "N13") (pinfunction "VDDARM_CAP_6_N13") (pintype "power_in"))
      (node (ref "U2") (pin "P11") (pinfunction "VDDARM23_CAP_7_P11") (pintype "power_in"))
      (node (ref "U2") (pin "P13") (pinfunction "VDDARM_CAP_7_P13") (pintype "power_in"))
      (node (ref "U2") (pin "R11") (pinfunction "VDDARM23_CAP_8_R11") (pintype "power_in"))
      (node (ref "U2") (pin "R13") (pinfunction "VDDARM_CAP_8_R13") (pintype "power_in"))
    )
    (net (code "8") (name "/+2V5_VDDHIGH_VPH") (class "Default")
      (node (ref "C104") (pin "1") (pinfunction "1_1") (pintype "passive"))
      (node (ref "C105") (pin "1") (pinfunction "1_1") (pintype "passive"))
      (node (ref "U2") (pin "H10") (pinfunction "VDDHIGH_CAP_1_H10") (pintype "power_in"))
      (node (ref "U2") (pin "J10") (pinfunction "VDDHIGH_CAP_2_J10") (pintype "power_in"))
    )
    (net (code "9") (name "/+NVCC_CSI") (class "Default")
      (node (ref "R55") (pin "1") (pinfunction "1_1") (pintype "passive"))
      (node (ref "U2") (pin "N7") (pinfunction "NVCC_CSI_N7") (pintype "power_in"))
    )
    (net (code "10") (name "/+VDDPU") (class "Default")
      (node (ref "C100") (pin "1") (pinfunction "1_1") (pintype "passive"))
      (node (ref "C95") (pin "1") (pinfunction "1_1") (pintype "passive"))
      (node (ref "C96") (pin "1") (pinfunction "1_1") (pintype "passive"))
      (node (ref "C97") (pin "1") (pinfunction "1_1") (pintype "passive"))
      (node (ref "C98") (pin "1") (pinfunction "1_1") (pintype "passive"))
      (node (ref "C99") (pin "1") (pinfunction "1_1") (pintype "passive"))
      (node (ref "U2") (pin "H17") (pinfunction "VDDPU_CAP_1_H17") (pintype "power_in"))
      (node (ref "U2") (pin "J17") (pinfunction "VDDPU_CAP_2_J17") (pintype "power_in"))
      (node (ref "U2") (pin "K17") (pinfunction "VDDPU_CAP_3_K17") (pintype "power_in"))
      (node (ref "U2") (pin "L17") (pinfunction "VDDPU_CAP_4_L17") (pintype "power_in"))
      (node (ref "U2") (pin "M17") (pinfunction "VDDPU_CAP_5_M17") (pintype "power_in"))
      (node (ref "U2") (pin "N17") (pinfunction "VDDPU_CAP_6_N17") (pintype "power_in"))
      (node (ref "U2") (pin "P17") (pinfunction "VDDPU_CAP_7_P17") (pintype "power_in"))
    )
    (net (code "11") (name "/+VDD_SNVS_CAP") (class "Default")
      (node (ref "C107") (pin "1") (pinfunction "1_1") (pintype "passive"))
      (node (ref "U2") (pin "G9") (pinfunction "VDD_SNVS_CAP_G9") (pintype "power_in"))
    )
    (net (code "12") (name "ARM_1V375") (class "Default")
      (node (ref "C87") (pin "1") (pinfunction "1_1") (pintype "passive"))
      (node (ref "C88") (pin "1") (pinfunction "1_1") (pintype "passive"))
      (node (ref "C89") (pin "1") (pinfunction "1_1") (pintype "passive"))
      (node (ref "C90") (pin "1") (pinfunction "1_1") (pintype "passive"))
      (node (ref "C91") (pin "1") (pinfunction "1_1") (pintype "passive"))
      (node (ref "C92") (pin "1") (pinfunction "1_1") (pintype "passive"))
      (node (ref "C93") (pin "1") (pinfunction "1_1") (pintype "passive"))
      (node (ref "C94") (pin "1") (pinfunction "1_1") (pintype "passive"))
      (node (ref "U2") (pin "H16") (pinfunction "VDDSOC_IN_1_H16") (pintype "power_in"))
      (node (ref "U2") (pin "J16") (pinfunction "VDDSOC_IN_2_J16") (pintype "power_in"))
      (node (ref "U2") (pin "K16") (pinfunction "VDDSOC_IN_3_K16") (pintype "power_in"))
      (node (ref "U2") (pin "L16") (pinfunction "VDDSOC_IN_4_L16") (pintype "power_in"))
      (node (ref "U2") (pin "M16") (pinfunction "VDDSOC_IN_5_M16") (pintype "power_in"))
      (node (ref "U2") (pin "N16") (pinfunction "VDDSOC_IN_6_N16") (pintype "power_in"))
      (node (ref "U2") (pin "P16") (pinfunction "VDDSOC_IN_7_P16") (pintype "power_in"))
      (node (ref "U2") (pin "R16") (pinfunction "VDDSOC_IN_8_R16") (pintype "power_in"))
      (node (ref "U2") (pin "T16") (pinfunction "VDDSOC_IN_9_T16") (pintype "power_in"))
      (node (ref "U2") (pin "U16") (pinfunction "VDDSOC_IN_10_U16") (pintype "power_in"))
    )
    (net (code "13") (name "GND") (class "Default")
      (node (ref "C100") (pin "2") (pinfunction "2_2") (pintype "passive"))
      (node (ref "C101") (pin "2") (pinfunction "2_2") (pintype "passive"))
      (node (ref "C102") (pin "2") (pinfunction "2_2") (pintype "passive"))
      (node (ref "C103") (pin "2") (pinfunction "2_2") (pintype "passive"))
      (node (ref "C104") (pin "2") (pinfunction "2_2") (pintype "passive"))
      (node (ref "C105") (pin "2") (pinfunction "2_2") (pintype "passive"))
      (node (ref "C106") (pin "2") (pinfunction "2_2") (pintype "passive"))
      (node (ref "C107") (pin "2") (pinfunction "2_2") (pintype "passive"))
      (node (ref "C108") (pin "2") (pinfunction "2_2") (pintype "passive"))
      (node (ref "C109") (pin "2") (pinfunction "2_2") (pintype "passive"))
      (node (ref "C110") (pin "2") (pinfunction "2_2") (pintype "passive"))
      (node (ref "C111") (pin "2") (pinfunction "2_2") (pintype "passive"))
      (node (ref "C112") (pin "2") (pinfunction "2_2") (pintype "passive"))
      (node (ref "C113") (pin "2") (pinfunction "2_2") (pintype "passive"))
      (node (ref "C114") (pin "2") (pinfunction "2_2") (pintype "passive"))
      (node (ref "C115") (pin "2") (pinfunction "2_2") (pintype "passive"))
      (node (ref "C116") (pin "2") (pinfunction "2_2") (pintype "passive"))
      (node (ref "C117") (pin "2") (pinfunction "2_2") (pintype "passive"))
      (node (ref "C118") (pin "2") (pinfunction "2_2") (pintype "passive"))
      (node (ref "C119") (pin "2") (pinfunction "2_2") (pintype "passive"))
      (node (ref "C120") (pin "2") (pinfunction "2_2") (pintype "passive"))
      (node (ref "C121") (pin "2") (pinfunction "2_2") (pintype "passive"))
      (node (ref "C122") (pin "2") (pinfunction "2_2") (pintype "passive"))
      (node (ref "C123") (pin "2") (pinfunction "2_2") (pintype "passive"))
      (node (ref "C124") (pin "2") (pinfunction "2_2") (pintype "passive"))
      (node (ref "C125") (pin "2") (pinfunction "2_2") (pintype "passive"))
      (node (ref "C126") (pin "2") (pinfunction "2_2") (pintype "passive"))
      (node (ref "C127") (pin "2") (pinfunction "2_2") (pintype "passive"))
      (node (ref "C128") (pin "2") (pinfunction "2_2") (pintype "passive"))
      (node (ref "C129") (pin "2") (pinfunction "2_2") (pintype "passive"))
      (node (ref "C130") (pin "2") (pinfunction "2_2") (pintype "passive"))
      (node (ref "C131") (pin "2") (pinfunction "2_2") (pintype "passive"))
      (node (ref "C132") (pin "2") (pinfunction "2_2") (pintype "passive"))
      (node (ref "C69") (pin "2") (pinfunction "2_2") (pintype "passive"))
      (node (ref "C70") (pin "2") (pinfunction "2_2") (pintype "passive"))
      (node (ref "C71") (pin "2") (pinfunction "2_2") (pintype "passive"))
      (node (ref "C72") (pin "2") (pinfunction "2_2") (pintype "passive"))
      (node (ref "C73") (pin "2") (pinfunction "2_2") (pintype "passive"))
      (node (ref "C74") (pin "2") (pinfunction "2_2") (pintype "passive"))
      (node (ref "C75") (pin "2") (pinfunction "2_2") (pintype "passive"))
      (node (ref "C76") (pin "2") (pinfunction "2_2") (pintype "passive"))
      (node (ref "C77") (pin "2") (pinfunction "2_2") (pintype "passive"))
      (node (ref "C78") (pin "2") (pinfunction "2_2") (pintype "passive"))
      (node (ref "C79") (pin "2") (pinfunction "2_2") (pintype "passive"))
      (node (ref "C80") (pin "2") (pinfunction "2_2") (pintype "passive"))
      (node (ref "C81") (pin "2") (pinfunction "2_2") (pintype "passive"))
      (node (ref "C82") (pin "2") (pinfunction "2_2") (pintype "passive"))
      (node (ref "C83") (pin "2") (pinfunction "2_2") (pintype "passive"))
      (node (ref "C84") (pin "2") (pinfunction "2_2") (pintype "passive"))
      (node (ref "C85") (pin "2") (pinfunction "2_2") (pintype "passive"))
      (node (ref "C86") (pin "2") (pinfunction "2_2") (pintype "passive"))
      (node (ref "C87") (pin "2") (pinfunction "2_2") (pintype "passive"))
      (node (ref "C88") (pin "2") (pinfunction "2_2") (pintype "passive"))
      (node (ref "C89") (pin "2") (pinfunction "2_2") (pintype "passive"))
      (node (ref "C90") (pin "2") (pinfunction "2_2") (pintype "passive"))
      (node (ref "C91") (pin "2") (pinfunction "2_2") (pintype "passive"))
      (node (ref "C92") (pin "2") (pinfunction "2_2") (pintype "passive"))
      (node (ref "C93") (pin "2") (pinfunction "2_2") (pintype "passive"))
      (node (ref "C94") (pin "2") (pinfunction "2_2") (pintype "passive"))
      (node (ref "C95") (pin "2") (pinfunction "2_2") (pintype "passive"))
      (node (ref "C96") (pin "2") (pinfunction "2_2") (pintype "passive"))
      (node (ref "C97") (pin "2") (pinfunction "2_2") (pintype "passive"))
      (node (ref "C98") (pin "2") (pinfunction "2_2") (pintype "passive"))
      (node (ref "C99") (pin "2") (pinfunction "2_2") (pintype "passive"))
      (node (ref "R57") (pin "1") (pinfunction "1_1") (pintype "passive"))
      (node (ref "U2") (pin "A13") (pinfunction "GND_1_A13") (pintype "power_in"))
      (node (ref "U2") (pin "A25") (pinfunction "GND_2_A25") (pintype "power_in"))
      (node (ref "U2") (pin "A4") (pinfunction "GND_3_A4") (pintype "power_in"))
      (node (ref "U2") (pin "A5") (pinfunction "FA_ANA_A5") (pintype "power_in"))
      (node (ref "U2") (pin "A8") (pinfunction "GND_4_A8") (pintype "power_in"))
      (node (ref "U2") (pin "AA10") (pinfunction "GND_5_AA10") (pintype "power_in"))
      (node (ref "U2") (pin "AA13") (pinfunction "GND_6_AA13") (pintype "power_in"))
      (node (ref "U2") (pin "AA16") (pinfunction "GND_7_AA16") (pintype "power_in"))
      (node (ref "U2") (pin "AA19") (pinfunction "GND_8_AA19") (pintype "power_in"))
      (node (ref "U2") (pin "AA22") (pinfunction "GND_9_AA22") (pintype "power_in"))
      (node (ref "U2") (pin "AA7") (pinfunction "GND_10_AA7") (pintype "power_in"))
      (node (ref "U2") (pin "AB24") (pinfunction "GND_11_AB24") (pintype "power_in"))
      (node (ref "U2") (pin "AB3") (pinfunction "GND_12_AB3") (pintype "power_in"))
      (node (ref "U2") (pin "AD10") (pinfunction "GND_13_AD10") (pintype "power_in"))
      (node (ref "U2") (pin "AD13") (pinfunction "GND_14_AD13") (pintype "power_in"))
      (node (ref "U2") (pin "AD16") (pinfunction "GND_15_AD16") (pintype "power_in"))
      (node (ref "U2") (pin "AD19") (pinfunction "GND_16_AD19") (pintype "power_in"))
      (node (ref "U2") (pin "AD22") (pinfunction "GND_17_AD22") (pintype "power_in"))
      (node (ref "U2") (pin "AD4") (pinfunction "GND_18_AD4") (pintype "power_in"))
      (node (ref "U2") (pin "AD7") (pinfunction "GND_19_AD7") (pintype "power_in"))
      (node (ref "U2") (pin "AE1") (pinfunction "GND_20_AE1") (pintype "power_in"))
      (node (ref "U2") (pin "AE25") (pinfunction "GND_21_AE25") (pintype "power_in"))
      (node (ref "U2") (pin "B4") (pinfunction "GND_22_B4") (pintype "power_in"))
      (node (ref "U2") (pin "B5") (pinfunction "VDD_FA_B5") (pintype "power_in"))
      (node (ref "U2") (pin "C1") (pinfunction "GND_23_C1") (pintype "power_in"))
      (node (ref "U2") (pin "C10") (pinfunction "GND_24_C10") (pintype "power_in"))
      (node (ref "U2") (pin "C4") (pinfunction "GND_25_C4") (pintype "power_in"))
      (node (ref "U2") (pin "C6") (pinfunction "GND_26_C6") (pintype "power_in"))
      (node (ref "U2") (pin "D3") (pinfunction "GND_27_D3") (pintype "power_in"))
      (node (ref "U2") (pin "D6") (pinfunction "GND_28_D6") (pintype "power_in"))
      (node (ref "U2") (pin "D8") (pinfunction "GND_29_D8") (pintype "power_in"))
      (node (ref "U2") (pin "E5") (pinfunction "GND_30_E5") (pintype "power_in"))
      (node (ref "U2") (pin "E6") (pinfunction "GND_31_E6") (pintype "power_in"))
      (node (ref "U2") (pin "E7") (pinfunction "GND_32_E7") (pintype "power_in"))
      (node (ref "U2") (pin "F5") (pinfunction "GND_33_F5") (pintype "power_in"))
      (node (ref "U2") (pin "F6") (pinfunction "GND_34_F6") (pintype "power_in"))
      (node (ref "U2") (pin "F7") (pinfunction "GND_35_F7") (pintype "power_in"))
      (node (ref "U2") (pin "F8") (pinfunction "GND_36_F8") (pintype "power_in"))
      (node (ref "U2") (pin "G10") (pinfunction "GND_37_G10") (pintype "power_in"))
      (node (ref "U2") (pin "G19") (pinfunction "GND_38_G19") (pintype "power_in"))
      (node (ref "U2") (pin "G3") (pinfunction "GND_39_G3") (pintype "power_in"))
      (node (ref "U2") (pin "H12") (pinfunction "GND_40_H12") (pintype "power_in"))
      (node (ref "U2") (pin "H15") (pinfunction "GND_41_H15") (pintype "power_in"))
      (node (ref "U2") (pin "H18") (pinfunction "GND_42_H18") (pintype "power_in"))
      (node (ref "U2") (pin "H8") (pinfunction "GND_43_H8") (pintype "power_in"))
      (node (ref "U2") (pin "J12") (pinfunction "GND_44_J12") (pintype "power_in"))
      (node (ref "U2") (pin "J15") (pinfunction "GND_45_J15") (pintype "power_in"))
      (node (ref "U2") (pin "J18") (pinfunction "GND_46_J18") (pintype "power_in"))
      (node (ref "U2") (pin "J2") (pinfunction "GND_47_J2") (pintype "power_in"))
      (node (ref "U2") (pin "J8") (pinfunction "GND_48_J8") (pintype "power_in"))
      (node (ref "U2") (pin "K10") (pinfunction "GND_49_K10") (pintype "power_in"))
      (node (ref "U2") (pin "K12") (pinfunction "GND_50_K12") (pintype "power_in"))
      (node (ref "U2") (pin "K15") (pinfunction "GND_51_K15") (pintype "power_in"))
      (node (ref "U2") (pin "K18") (pinfunction "GND_52_K18") (pintype "power_in"))
      (node (ref "U2") (pin "K8") (pinfunction "GND_53_K8") (pintype "power_in"))
      (node (ref "U2") (pin "L10") (pinfunction "GND_54_L10") (pintype "power_in"))
      (node (ref "U2") (pin "L12") (pinfunction "GND_55_L12") (pintype "power_in"))
      (node (ref "U2") (pin "L15") (pinfunction "GND_56_L15") (pintype "power_in"))
      (node (ref "U2") (pin "L18") (pinfunction "GND_57_L18") (pintype "power_in"))
      (node (ref "U2") (pin "L2") (pinfunction "GND_58_L2") (pintype "power_in"))
      (node (ref "U2") (pin "L5") (pinfunction "GND_59_L5") (pintype "power_in"))
      (node (ref "U2") (pin "L8") (pinfunction "GND_60_L8") (pintype "power_in"))
      (node (ref "U2") (pin "M10") (pinfunction "GND_61_M10") (pintype "power_in"))
      (node (ref "U2") (pin "M12") (pinfunction "GND_62_M12") (pintype "power_in"))
      (node (ref "U2") (pin "M15") (pinfunction "GND_63_M15") (pintype "power_in"))
      (node (ref "U2") (pin "M18") (pinfunction "GND_64_M18") (pintype "power_in"))
      (node (ref "U2") (pin "M8") (pinfunction "GND_65_M8") (pintype "power_in"))
      (node (ref "U2") (pin "N10") (pinfunction "GND_66_N10") (pintype "power_in"))
      (node (ref "U2") (pin "N15") (pinfunction "GND_67_N15") (pintype "power_in"))
      (node (ref "U2") (pin "N18") (pinfunction "GND_68_N18") (pintype "power_in"))
      (node (ref "U2") (pin "N8") (pinfunction "GND_69_N8") (pintype "power_in"))
      (node (ref "U2") (pin "P10") (pinfunction "GND_70_P10") (pintype "power_in"))
      (node (ref "U2") (pin "P12") (pinfunction "GND_71_P12") (pintype "power_in"))
      (node (ref "U2") (pin "P15") (pinfunction "GND_72_P15") (pintype "power_in"))
      (node (ref "U2") (pin "P18") (pinfunction "GND_73_P18") (pintype "power_in"))
      (node (ref "U2") (pin "P8") (pinfunction "GND_74_P8") (pintype "power_in"))
      (node (ref "U2") (pin "R12") (pinfunction "GND_75_R12") (pintype "power_in"))
      (node (ref "U2") (pin "R15") (pinfunction "GND_76_R15") (pintype "power_in"))
      (node (ref "U2") (pin "R17") (pinfunction "GND_77_R17") (pintype "power_in"))
      (node (ref "U2") (pin "R8") (pinfunction "GND_78_R8") (pintype "power_in"))
      (node (ref "U2") (pin "T11") (pinfunction "GND_79_T11") (pintype "power_in"))
      (node (ref "U2") (pin "T12") (pinfunction "GND_80_T12") (pintype "power_in"))
      (node (ref "U2") (pin "T15") (pinfunction "GND_81_T15") (pintype "power_in"))
      (node (ref "U2") (pin "T17") (pinfunction "GND_82_T17") (pintype "power_in"))
      (node (ref "U2") (pin "T19") (pinfunction "GND_83_T19") (pintype "power_in"))
      (node (ref "U2") (pin "T8") (pinfunction "GND_84_T8") (pintype "power_in"))
      (node (ref "U2") (pin "U11") (pinfunction "GND_85_U11") (pintype "power_in"))
      (node (ref "U2") (pin "U12") (pinfunction "GND_86_U12") (pintype "power_in"))
      (node (ref "U2") (pin "U15") (pinfunction "GND_87_U15") (pintype "power_in"))
      (node (ref "U2") (pin "U17") (pinfunction "GND_88_U17") (pintype "power_in"))
      (node (ref "U2") (pin "U19") (pinfunction "GND_90_U19") (pintype "power_in"))
      (node (ref "U2") (pin "U8") (pinfunction "GND_89_U8") (pintype "power_in"))
      (node (ref "U2") (pin "V19") (pinfunction "GND_92_V19") (pintype "power_in"))
      (node (ref "U2") (pin "V8") (pinfunction "GND_91_V8") (pintype "power_in"))
      (node (ref "U2") (pin "W10") (pinfunction "GND_97_W10") (pintype "power_in"))
      (node (ref "U2") (pin "W11") (pinfunction "GND_98_W11") (pintype "power_in"))
      (node (ref "U2") (pin "W12") (pinfunction "GND_99_W12") (pintype "power_in"))
      (node (ref "U2") (pin "W13") (pinfunction "GND_100_W13") (pintype "power_in"))
      (node (ref "U2") (pin "W15") (pinfunction "GND_101_W15") (pintype "power_in"))
      (node (ref "U2") (pin "W16") (pinfunction "GND_102_W16") (pintype "power_in"))
      (node (ref "U2") (pin "W17") (pinfunction "GND_103_W17") (pintype "power_in"))
      (node (ref "U2") (pin "W18") (pinfunction "GND_104_W18") (pintype "power_in"))
      (node (ref "U2") (pin "W19") (pinfunction "GND_105_W19") (pintype "power_in"))
      (node (ref "U2") (pin "W3") (pinfunction "GND_93_W3") (pintype "power_in"))
      (node (ref "U2") (pin "W7") (pinfunction "GND_94_W7") (pintype "power_in"))
      (node (ref "U2") (pin "W8") (pinfunction "GND_95_W8") (pintype "power_in"))
      (node (ref "U2") (pin "W9") (pinfunction "GND_96_W9") (pintype "power_in"))
      (node (ref "U2") (pin "Y24") (pinfunction "GND_107_Y24") (pintype "power_in"))
      (node (ref "U2") (pin "Y5") (pinfunction "GND_106_Y5") (pintype "power_in"))
    )
    (net (code "14") (name "SOC_1V375") (class "Default")
      (node (ref "C69") (pin "1") (pinfunction "1_1") (pintype "passive"))
      (node (ref "C70") (pin "1") (pinfunction "1_1") (pintype "passive"))
      (node (ref "C71") (pin "1") (pinfunction "1_1") (pintype "passive"))
      (node (ref "C72") (pin "1") (pinfunction "1_1") (pintype "passive"))
      (node (ref "C73") (pin "1") (pinfunction "1_1") (pintype "passive"))
      (node (ref "C78") (pin "1") (pinfunction "1_1") (pintype "passive"))
      (node (ref "C79") (pin "1") (pinfunction "1_1") (pintype "passive"))
      (node (ref "C80") (pin "1") (pinfunction "1_1") (pintype "passive"))
      (node (ref "C81") (pin "1") (pinfunction "1_1") (pintype "passive"))
      (node (ref "R56") (pin "1") (pinfunction "1_1") (pintype "passive"))
      (node (ref "U2") (pin "H14") (pinfunction "VDDARM_IN_1_H14") (pintype "power_in"))
      (node (ref "U2") (pin "J14") (pinfunction "VDDARM_IN_2_J14") (pintype "power_in"))
      (node (ref "U2") (pin "K14") (pinfunction "VDDARM_IN_3_K14") (pintype "power_in"))
      (node (ref "U2") (pin "K9") (pinfunction "VDDARM23_IN_1_K9") (pintype "power_in"))
      (node (ref "U2") (pin "L14") (pinfunction "VDDARM_IN_4_L14") (pintype "power_in"))
      (node (ref "U2") (pin "L9") (pinfunction "VDDARM23_IN_2_L9") (pintype "power_in"))
      (node (ref "U2") (pin "M14") (pinfunction "VDDARM_IN_5_M14") (pintype "power_in"))
      (node (ref "U2") (pin "M9") (pinfunction "VDDARM23_IN_3_M9") (pintype "power_in"))
      (node (ref "U2") (pin "N14") (pinfunction "VDDARM_IN_6_N14") (pintype "power_in"))
      (node (ref "U2") (pin "N9") (pinfunction "VDDARM23_IN_4_N9") (pintype "power_in"))
      (node (ref "U2") (pin "P14") (pinfunction "VDDARM_IN_7_P14") (pintype "power_in"))
      (node (ref "U2") (pin "P9") (pinfunction "VDDARM23_IN_5_P9") (pintype "power_in"))
      (node (ref "U2") (pin "R14") (pinfunction "VDDARM_IN_8_R14") (pintype "power_in"))
      (node (ref "U2") (pin "R9") (pinfunction "VDDARM23_IN_6_R9") (pintype "power_in"))
      (node (ref "U2") (pin "T9") (pinfunction "VDDARM23_IN_7_T9") (pintype "power_in"))
      (node (ref "U2") (pin "U9") (pinfunction "VDDARM23_IN_8_U9") (pintype "power_in"))
    )
    (net (code "15") (name "unconnected-(U2B-GPANAIO-PadC8)") (class "Default")
      (node (ref "U2") (pin "C8") (pinfunction "GPANAIO_C8") (pintype "power_in+no_connect"))
    )
  )
)
